# typeCounter.net
KiCad netlist of a schematic drawn in Altium Designer
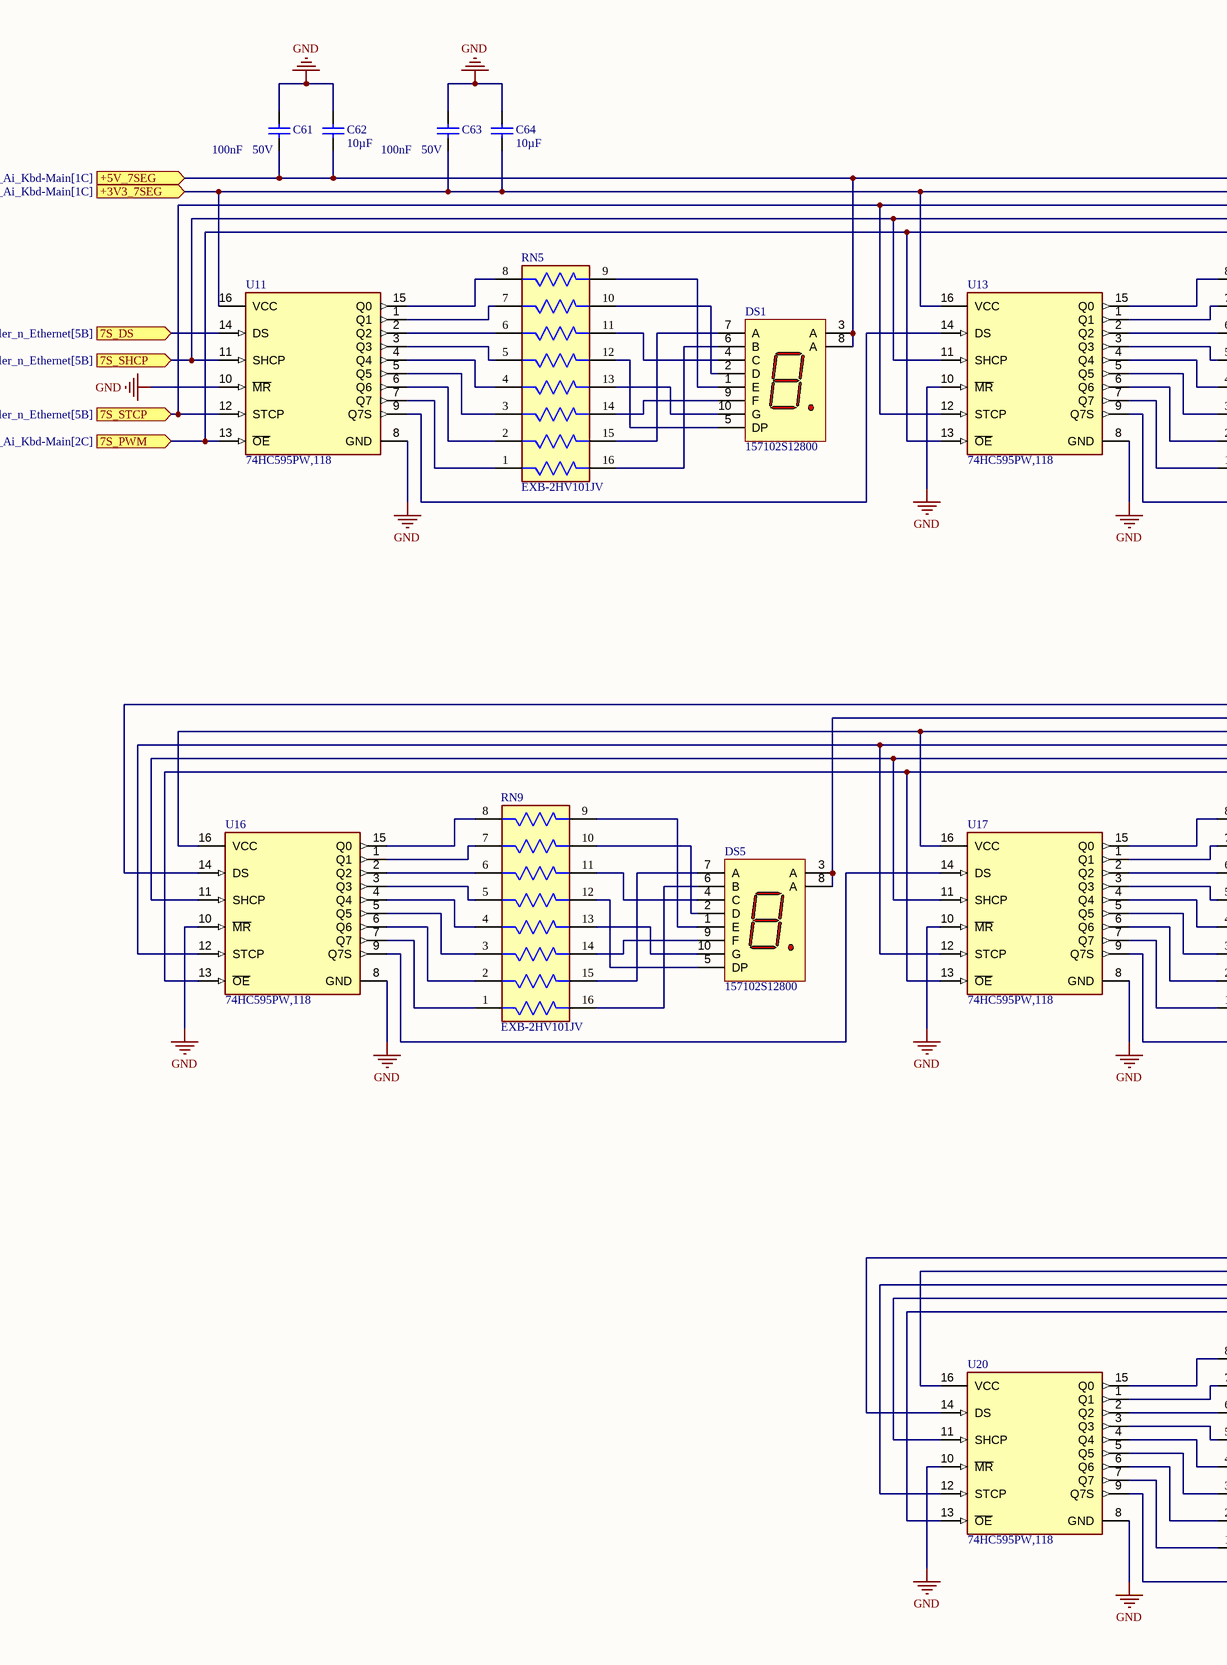
[diagram p0: typeCounter.SchDoc, left]
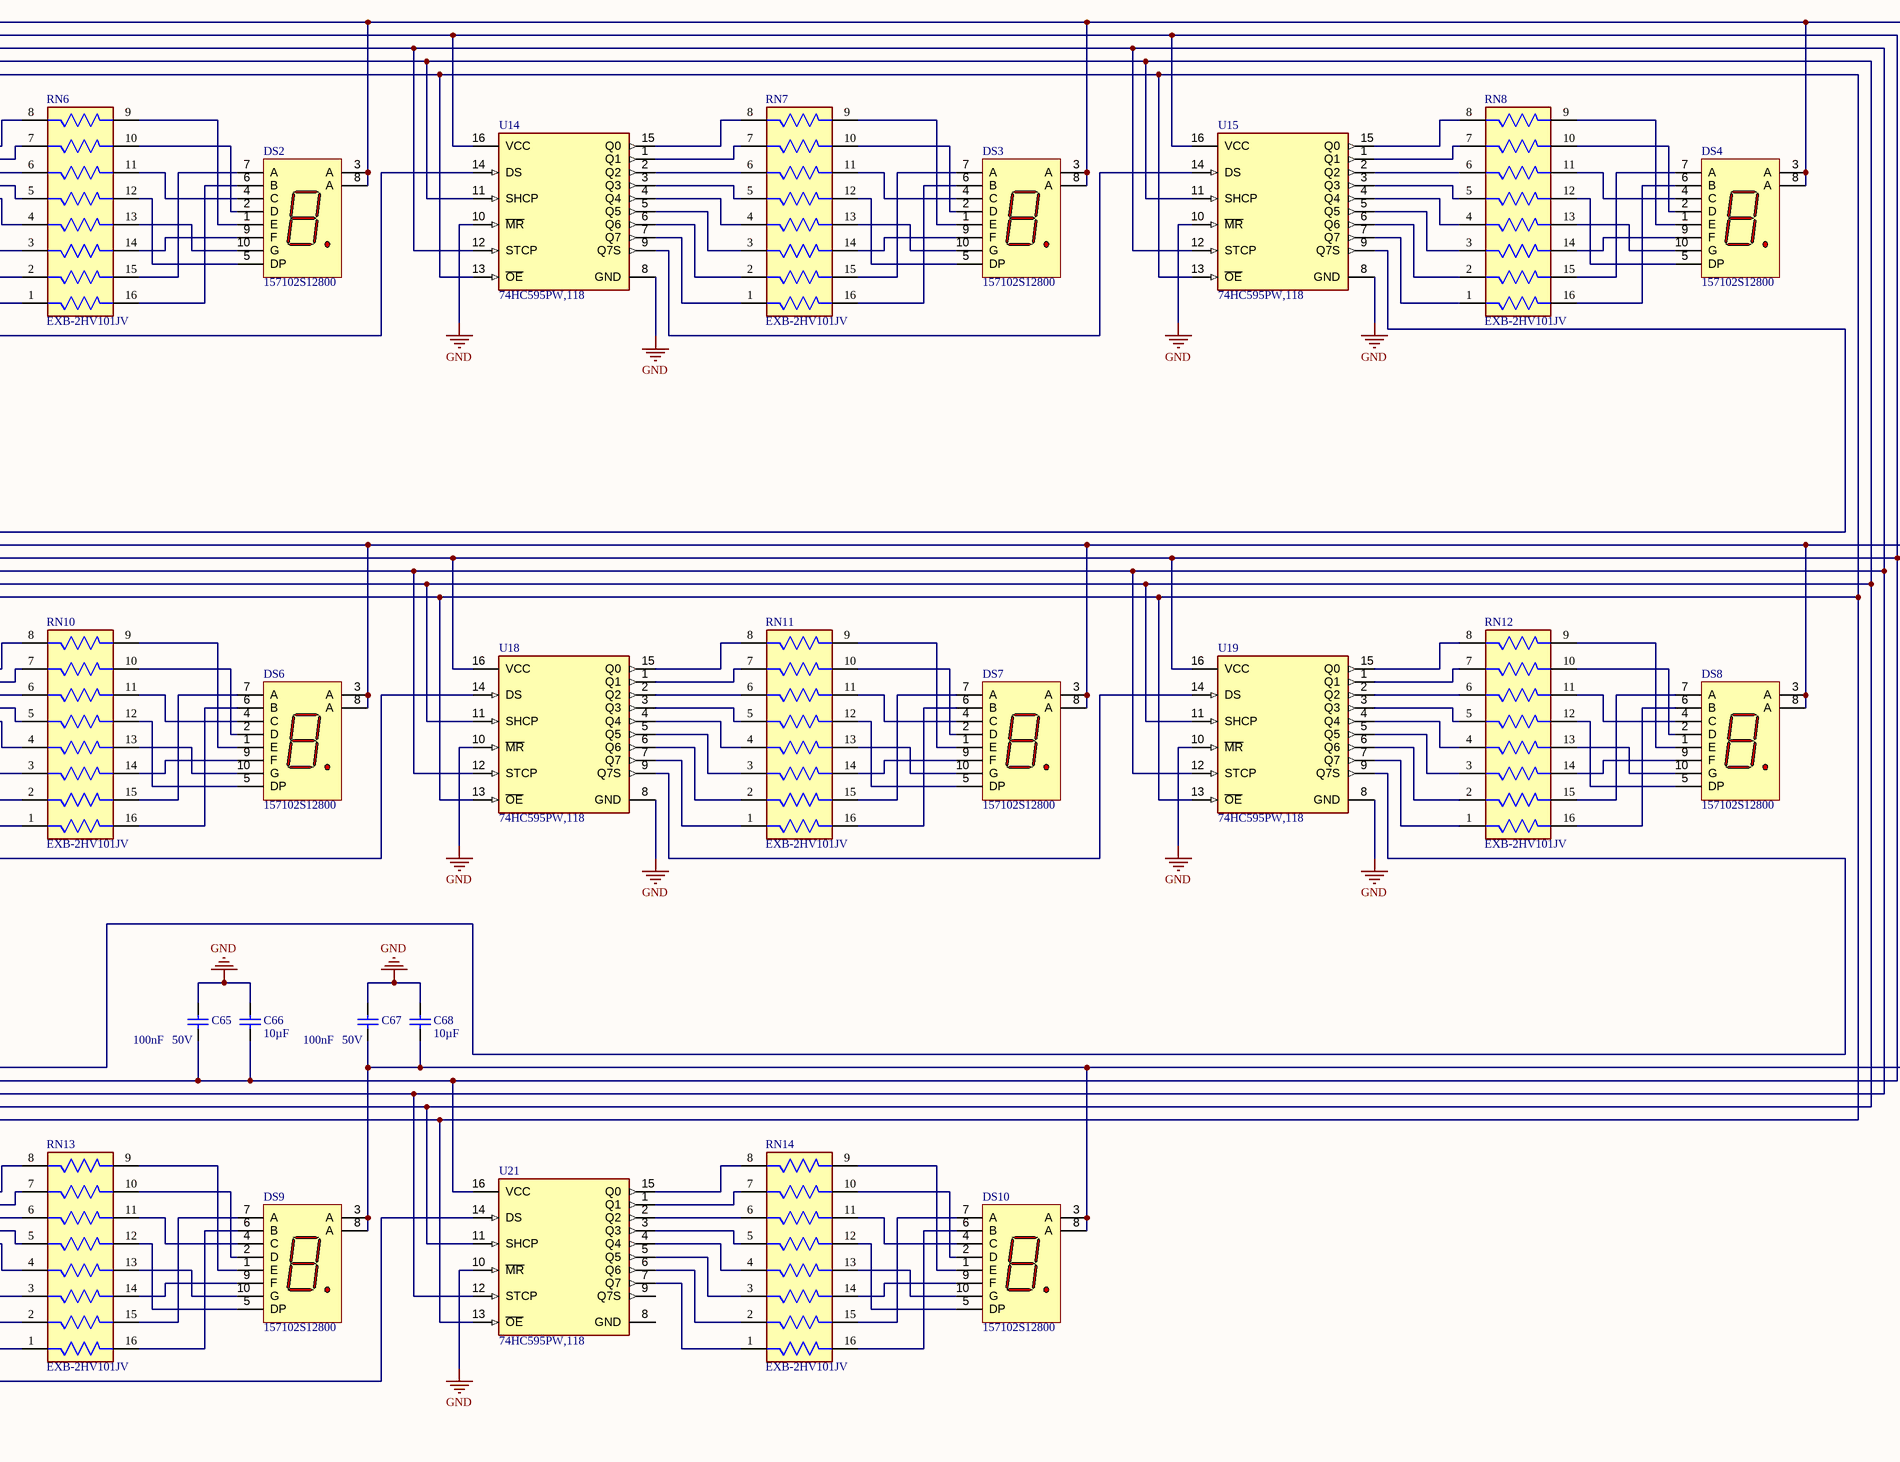
[diagram p1: typeCounter.SchDoc, right]

(export (version "E")
  (design (tool "Eeschema 10.0.6"))
  (components
    (comp (ref "C61")
      (value "885012206095")
      (footprint "WCAP-CSGP_0603_L1.6W0.8H0.8_Reflow")
      (description "WCAP-CSGP Multilayer Ceramic Chip Capacitor, General Purpose, size 0603, X7R, 100nF, 50VDC")
      (fields
        (field (name "CAPACITANCE") "100nF")
        (field (name "MANUFACTURER") "Wurth Elektronik")
        (field (name "RATED VOLTAGE (DC)") "50V")
      )
      (libsource (lib "Test365") (part "885012209047R"))
    )
    (comp (ref "C62")
      (value "885012106006")
      (footprint "WCAP-CSGP_0603_L1.6W0.8H0.8_Reflow")
      (description "WCAP-CSGP Multilayer Ceramic Chip Capacitor, General Purpose, size 0603, X5R, 10µF, 6.3VDC")
      (fields (field (name "MANUFACTURER") "Wurth Elektronik") (field (name "CAPACITANCE") "10µF"))
      (libsource (lib "Test365") (part "885012209047R"))
    )
    (comp (ref "C63")
      (value "885012206095")
      (footprint "WCAP-CSGP_0603_L1.6W0.8H0.8_Reflow")
      (description "WCAP-CSGP Multilayer Ceramic Chip Capacitor, General Purpose, size 0603, X7R, 100nF, 50VDC")
      (fields
        (field (name "CAPACITANCE") "100nF")
        (field (name "MANUFACTURER") "Wurth Elektronik")
        (field (name "RATED VOLTAGE (DC)") "50V")
      )
      (libsource (lib "Test365") (part "885012209047R"))
    )
    (comp (ref "C64")
      (value "885012106006")
      (footprint "WCAP-CSGP_0603_L1.6W0.8H0.8_Reflow")
      (description "WCAP-CSGP Multilayer Ceramic Chip Capacitor, General Purpose, size 0603, X5R, 10µF, 6.3VDC")
      (fields (field (name "MANUFACTURER") "Wurth Elektronik") (field (name "CAPACITANCE") "10µF"))
      (libsource (lib "Test365") (part "885012209047R"))
    )
    (comp (ref "C65")
      (value "885012206095")
      (footprint "WCAP-CSGP_0603_L1.6W0.8H0.8_Reflow")
      (description "WCAP-CSGP Multilayer Ceramic Chip Capacitor, General Purpose, size 0603, X7R, 100nF, 50VDC")
      (fields
        (field (name "CAPACITANCE") "100nF")
        (field (name "MANUFACTURER") "Wurth Elektronik")
        (field (name "RATED VOLTAGE (DC)") "50V")
      )
      (libsource (lib "Test365") (part "885012209047R"))
    )
    (comp (ref "C66")
      (value "885012106006")
      (footprint "WCAP-CSGP_0603_L1.6W0.8H0.8_Reflow")
      (description "WCAP-CSGP Multilayer Ceramic Chip Capacitor, General Purpose, size 0603, X5R, 10µF, 6.3VDC")
      (fields (field (name "MANUFACTURER") "Wurth Elektronik") (field (name "CAPACITANCE") "10µF"))
      (libsource (lib "Test365") (part "885012209047R"))
    )
    (comp (ref "C67")
      (value "885012206095")
      (footprint "WCAP-CSGP_0603_L1.6W0.8H0.8_Reflow")
      (description "WCAP-CSGP Multilayer Ceramic Chip Capacitor, General Purpose, size 0603, X7R, 100nF, 50VDC")
      (fields
        (field (name "CAPACITANCE") "100nF")
        (field (name "MANUFACTURER") "Wurth Elektronik")
        (field (name "RATED VOLTAGE (DC)") "50V")
      )
      (libsource (lib "Test365") (part "885012209047R"))
    )
    (comp (ref "C68")
      (value "885012106006")
      (footprint "WCAP-CSGP_0603_L1.6W0.8H0.8_Reflow")
      (description "WCAP-CSGP Multilayer Ceramic Chip Capacitor, General Purpose, size 0603, X5R, 10µF, 6.3VDC")
      (fields (field (name "MANUFACTURER") "Wurth Elektronik") (field (name "CAPACITANCE") "10µF"))
      (libsource (lib "Test365") (part "885012209047R"))
    )
    (comp (ref "DS1")
      (value "157102S12800")
      (footprint "WL-S7DS_L10W6.9H3")
      (description "157102S12800 WL-S7DS 7 Segments Display SMT Single Digit")
      (libsource (lib "Altium Content Vault") (part "7 Segments_Red_CA_type 1"))
    )
    (comp (ref "DS2")
      (value "157102S12800")
      (footprint "WL-S7DS_L10W6.9H3")
      (description "157102S12800 WL-S7DS 7 Segments Display SMT Single Digit")
      (libsource (lib "Altium Content Vault") (part "7 Segments_Red_CA_type 1"))
    )
    (comp (ref "DS3")
      (value "157102S12800")
      (footprint "WL-S7DS_L10W6.9H3")
      (description "157102S12800 WL-S7DS 7 Segments Display SMT Single Digit")
      (libsource (lib "Altium Content Vault") (part "7 Segments_Red_CA_type 1"))
    )
    (comp (ref "DS4")
      (value "157102S12800")
      (footprint "WL-S7DS_L10W6.9H3")
      (description "157102S12800 WL-S7DS 7 Segments Display SMT Single Digit")
      (libsource (lib "Altium Content Vault") (part "7 Segments_Red_CA_type 1"))
    )
    (comp (ref "DS5")
      (value "157102S12800")
      (footprint "WL-S7DS_L10W6.9H3")
      (description "157102S12800 WL-S7DS 7 Segments Display SMT Single Digit")
      (libsource (lib "Altium Content Vault") (part "7 Segments_Red_CA_type 1"))
    )
    (comp (ref "DS6")
      (value "157102S12800")
      (footprint "WL-S7DS_L10W6.9H3")
      (description "157102S12800 WL-S7DS 7 Segments Display SMT Single Digit")
      (libsource (lib "Altium Content Vault") (part "7 Segments_Red_CA_type 1"))
    )
    (comp (ref "DS7")
      (value "157102S12800")
      (footprint "WL-S7DS_L10W6.9H3")
      (description "157102S12800 WL-S7DS 7 Segments Display SMT Single Digit")
      (libsource (lib "Altium Content Vault") (part "7 Segments_Red_CA_type 1"))
    )
    (comp (ref "DS8")
      (value "157102S12800")
      (footprint "WL-S7DS_L10W6.9H3")
      (description "157102S12800 WL-S7DS 7 Segments Display SMT Single Digit")
      (libsource (lib "Altium Content Vault") (part "7 Segments_Red_CA_type 1"))
    )
    (comp (ref "DS9")
      (value "157102S12800")
      (footprint "WL-S7DS_L10W6.9H3")
      (description "157102S12800 WL-S7DS 7 Segments Display SMT Single Digit")
      (libsource (lib "Altium Content Vault") (part "7 Segments_Red_CA_type 1"))
    )
    (comp (ref "DS10")
      (value "157102S12800")
      (footprint "WL-S7DS_L10W6.9H3")
      (description "157102S12800 WL-S7DS 7 Segments Display SMT Single Digit")
      (libsource (lib "Altium Content Vault") (part "7 Segments_Red_CA_type 1"))
    )
    (comp (ref "RN5")
      (value "EXB-2HV101JV")
      (footprint "FP-EXB2HV-MFG")
      (description "RES ARRAY 8 RES 100 OHM 1506")
      (fields (field (name "TOLERANCE") "5%"))
      (libsource (lib "Altium Content Vault") (part "42159c3963beb1554014d4041102c8c"))
    )
    (comp (ref "RN6")
      (value "EXB-2HV101JV")
      (footprint "FP-EXB2HV-MFG")
      (description "RES ARRAY 8 RES 100 OHM 1506")
      (fields (field (name "TOLERANCE") "5%"))
      (libsource (lib "Altium Content Vault") (part "42159c3963beb1554014d4041102c8c"))
    )
    (comp (ref "RN7")
      (value "EXB-2HV101JV")
      (footprint "FP-EXB2HV-MFG")
      (description "RES ARRAY 8 RES 100 OHM 1506")
      (fields (field (name "TOLERANCE") "5%"))
      (libsource (lib "Altium Content Vault") (part "42159c3963beb1554014d4041102c8c"))
    )
    (comp (ref "RN8")
      (value "EXB-2HV101JV")
      (footprint "FP-EXB2HV-MFG")
      (description "RES ARRAY 8 RES 100 OHM 1506")
      (fields (field (name "TOLERANCE") "5%"))
      (libsource (lib "Altium Content Vault") (part "42159c3963beb1554014d4041102c8c"))
    )
    (comp (ref "RN9")
      (value "EXB-2HV101JV")
      (footprint "FP-EXB2HV-MFG")
      (description "RES ARRAY 8 RES 100 OHM 1506")
      (fields (field (name "TOLERANCE") "5%"))
      (libsource (lib "Altium Content Vault") (part "42159c3963beb1554014d4041102c8c"))
    )
    (comp (ref "RN10")
      (value "EXB-2HV101JV")
      (footprint "FP-EXB2HV-MFG")
      (description "RES ARRAY 8 RES 100 OHM 1506")
      (fields (field (name "TOLERANCE") "5%"))
      (libsource (lib "Altium Content Vault") (part "42159c3963beb1554014d4041102c8c"))
    )
    (comp (ref "RN11")
      (value "EXB-2HV101JV")
      (footprint "FP-EXB2HV-MFG")
      (description "RES ARRAY 8 RES 100 OHM 1506")
      (fields (field (name "TOLERANCE") "5%"))
      (libsource (lib "Altium Content Vault") (part "42159c3963beb1554014d4041102c8c"))
    )
    (comp (ref "RN12")
      (value "EXB-2HV101JV")
      (footprint "FP-EXB2HV-MFG")
      (description "RES ARRAY 8 RES 100 OHM 1506")
      (fields (field (name "TOLERANCE") "5%"))
      (libsource (lib "Altium Content Vault") (part "42159c3963beb1554014d4041102c8c"))
    )
    (comp (ref "RN13")
      (value "EXB-2HV101JV")
      (footprint "FP-EXB2HV-MFG")
      (description "RES ARRAY 8 RES 100 OHM 1506")
      (fields (field (name "TOLERANCE") "5%"))
      (libsource (lib "Altium Content Vault") (part "42159c3963beb1554014d4041102c8c"))
    )
    (comp (ref "RN14")
      (value "EXB-2HV101JV")
      (footprint "FP-EXB2HV-MFG")
      (description "RES ARRAY 8 RES 100 OHM 1506")
      (fields (field (name "TOLERANCE") "5%"))
      (libsource (lib "Altium Content Vault") (part "42159c3963beb1554014d4041102c8c"))
    )
    (comp (ref "U11")
      (value "74HC595PW,118")
      (footprint "FP-SOT403-1-MFG")
      (description "IC SHIFT REGISTER 8BIT 16TSSOP")
      (libsource (lib "Altium Content Vault") (part "27683e23285b137cd268a0f18c66bed"))
    )
    (comp (ref "U13")
      (value "74HC595PW,118")
      (footprint "FP-SOT403-1-MFG")
      (description "IC SHIFT REGISTER 8BIT 16TSSOP")
      (libsource (lib "Altium Content Vault") (part "27683e23285b137cd268a0f18c66bed"))
    )
    (comp (ref "U14")
      (value "74HC595PW,118")
      (footprint "FP-SOT403-1-MFG")
      (description "IC SHIFT REGISTER 8BIT 16TSSOP")
      (libsource (lib "Altium Content Vault") (part "27683e23285b137cd268a0f18c66bed"))
    )
    (comp (ref "U15")
      (value "74HC595PW,118")
      (footprint "FP-SOT403-1-MFG")
      (description "IC SHIFT REGISTER 8BIT 16TSSOP")
      (libsource (lib "Altium Content Vault") (part "27683e23285b137cd268a0f18c66bed"))
    )
    (comp (ref "U16")
      (value "74HC595PW,118")
      (footprint "FP-SOT403-1-MFG")
      (description "IC SHIFT REGISTER 8BIT 16TSSOP")
      (libsource (lib "Altium Content Vault") (part "27683e23285b137cd268a0f18c66bed"))
    )
    (comp (ref "U17")
      (value "74HC595PW,118")
      (footprint "FP-SOT403-1-MFG")
      (description "IC SHIFT REGISTER 8BIT 16TSSOP")
      (libsource (lib "Altium Content Vault") (part "27683e23285b137cd268a0f18c66bed"))
    )
    (comp (ref "U18")
      (value "74HC595PW,118")
      (footprint "FP-SOT403-1-MFG")
      (description "IC SHIFT REGISTER 8BIT 16TSSOP")
      (libsource (lib "Altium Content Vault") (part "27683e23285b137cd268a0f18c66bed"))
    )
    (comp (ref "U19")
      (value "74HC595PW,118")
      (footprint "FP-SOT403-1-MFG")
      (description "IC SHIFT REGISTER 8BIT 16TSSOP")
      (libsource (lib "Altium Content Vault") (part "27683e23285b137cd268a0f18c66bed"))
    )
    (comp (ref "U20")
      (value "74HC595PW,118")
      (footprint "FP-SOT403-1-MFG")
      (description "IC SHIFT REGISTER 8BIT 16TSSOP")
      (libsource (lib "Altium Content Vault") (part "27683e23285b137cd268a0f18c66bed"))
    )
    (comp (ref "U21")
      (value "74HC595PW,118")
      (footprint "FP-SOT403-1-MFG")
      (description "IC SHIFT REGISTER 8BIT 16TSSOP")
      (libsource (lib "Altium Content Vault") (part "27683e23285b137cd268a0f18c66bed"))
    )
  )
  (nets
    (net (code "1") (name "/+3V3_7SEG") (class "Default")
      (node (ref "C63") (pin "1") (pinfunction "1_1") (pintype "passive"))
      (node (ref "C64") (pin "1") (pinfunction "1_1") (pintype "passive"))
      (node (ref "C65") (pin "1") (pinfunction "1_1") (pintype "passive"))
      (node (ref "C66") (pin "1") (pinfunction "1_1") (pintype "passive"))
      (node (ref "U11") (pin "16") (pinfunction "VCC_16") (pintype "power_in"))
      (node (ref "U13") (pin "16") (pinfunction "VCC_16") (pintype "power_in"))
      (node (ref "U14") (pin "16") (pinfunction "VCC_16") (pintype "power_in"))
      (node (ref "U15") (pin "16") (pinfunction "VCC_16") (pintype "power_in"))
      (node (ref "U16") (pin "16") (pinfunction "VCC_16") (pintype "power_in"))
      (node (ref "U17") (pin "16") (pinfunction "VCC_16") (pintype "power_in"))
      (node (ref "U18") (pin "16") (pinfunction "VCC_16") (pintype "power_in"))
      (node (ref "U19") (pin "16") (pinfunction "VCC_16") (pintype "power_in"))
      (node (ref "U20") (pin "16") (pinfunction "VCC_16") (pintype "power_in"))
      (node (ref "U21") (pin "16") (pinfunction "VCC_16") (pintype "power_in"))
    )
    (net (code "2") (name "/+5V_7SEG") (class "Default")
      (node (ref "C61") (pin "1") (pinfunction "1_1") (pintype "passive"))
      (node (ref "C62") (pin "1") (pinfunction "1_1") (pintype "passive"))
      (node (ref "C67") (pin "1") (pinfunction "1_1") (pintype "passive"))
      (node (ref "C68") (pin "1") (pinfunction "1_1") (pintype "passive"))
      (node (ref "DS1") (pin "3") (pinfunction "A_3") (pintype "passive"))
      (node (ref "DS1") (pin "8") (pinfunction "A_8") (pintype "passive"))
      (node (ref "DS10") (pin "3") (pinfunction "A_3") (pintype "passive"))
      (node (ref "DS10") (pin "8") (pinfunction "A_8") (pintype "passive"))
      (node (ref "DS2") (pin "3") (pinfunction "A_3") (pintype "passive"))
      (node (ref "DS2") (pin "8") (pinfunction "A_8") (pintype "passive"))
      (node (ref "DS3") (pin "3") (pinfunction "A_3") (pintype "passive"))
      (node (ref "DS3") (pin "8") (pinfunction "A_8") (pintype "passive"))
      (node (ref "DS4") (pin "3") (pinfunction "A_3") (pintype "passive"))
      (node (ref "DS4") (pin "8") (pinfunction "A_8") (pintype "passive"))
      (node (ref "DS5") (pin "3") (pinfunction "A_3") (pintype "passive"))
      (node (ref "DS5") (pin "8") (pinfunction "A_8") (pintype "passive"))
      (node (ref "DS6") (pin "3") (pinfunction "A_3") (pintype "passive"))
      (node (ref "DS6") (pin "8") (pinfunction "A_8") (pintype "passive"))
      (node (ref "DS7") (pin "3") (pinfunction "A_3") (pintype "passive"))
      (node (ref "DS7") (pin "8") (pinfunction "A_8") (pintype "passive"))
      (node (ref "DS8") (pin "3") (pinfunction "A_3") (pintype "passive"))
      (node (ref "DS8") (pin "8") (pinfunction "A_8") (pintype "passive"))
      (node (ref "DS9") (pin "3") (pinfunction "A_3") (pintype "passive"))
      (node (ref "DS9") (pin "8") (pinfunction "A_8") (pintype "passive"))
    )
    (net (code "3") (name "/7S_DS") (class "Default")
      (node (ref "U11") (pin "14") (pinfunction "DS_14") (pintype "input"))
    )
    (net (code "4") (name "/7S_PWM") (class "Default")
      (node (ref "U11") (pin "13") (pinfunction "~{OE}_13") (pintype "input"))
      (node (ref "U13") (pin "13") (pinfunction "~{OE}_13") (pintype "input"))
      (node (ref "U14") (pin "13") (pinfunction "~{OE}_13") (pintype "input"))
      (node (ref "U15") (pin "13") (pinfunction "~{OE}_13") (pintype "input"))
      (node (ref "U16") (pin "13") (pinfunction "~{OE}_13") (pintype "input"))
      (node (ref "U17") (pin "13") (pinfunction "~{OE}_13") (pintype "input"))
      (node (ref "U18") (pin "13") (pinfunction "~{OE}_13") (pintype "input"))
      (node (ref "U19") (pin "13") (pinfunction "~{OE}_13") (pintype "input"))
      (node (ref "U20") (pin "13") (pinfunction "~{OE}_13") (pintype "input"))
      (node (ref "U21") (pin "13") (pinfunction "~{OE}_13") (pintype "input"))
    )
    (net (code "5") (name "/7S_SHCP") (class "Default")
      (node (ref "U11") (pin "11") (pinfunction "SHCP_11") (pintype "input"))
      (node (ref "U13") (pin "11") (pinfunction "SHCP_11") (pintype "input"))
      (node (ref "U14") (pin "11") (pinfunction "SHCP_11") (pintype "input"))
      (node (ref "U15") (pin "11") (pinfunction "SHCP_11") (pintype "input"))
      (node (ref "U16") (pin "11") (pinfunction "SHCP_11") (pintype "input"))
      (node (ref "U17") (pin "11") (pinfunction "SHCP_11") (pintype "input"))
      (node (ref "U18") (pin "11") (pinfunction "SHCP_11") (pintype "input"))
      (node (ref "U19") (pin "11") (pinfunction "SHCP_11") (pintype "input"))
      (node (ref "U20") (pin "11") (pinfunction "SHCP_11") (pintype "input"))
      (node (ref "U21") (pin "11") (pinfunction "SHCP_11") (pintype "input"))
    )
    (net (code "6") (name "/7S_STCP") (class "Default")
      (node (ref "U11") (pin "12") (pinfunction "STCP_12") (pintype "input"))
      (node (ref "U13") (pin "12") (pinfunction "STCP_12") (pintype "input"))
      (node (ref "U14") (pin "12") (pinfunction "STCP_12") (pintype "input"))
      (node (ref "U15") (pin "12") (pinfunction "STCP_12") (pintype "input"))
      (node (ref "U16") (pin "12") (pinfunction "STCP_12") (pintype "input"))
      (node (ref "U17") (pin "12") (pinfunction "STCP_12") (pintype "input"))
      (node (ref "U18") (pin "12") (pinfunction "STCP_12") (pintype "input"))
      (node (ref "U19") (pin "12") (pinfunction "STCP_12") (pintype "input"))
      (node (ref "U20") (pin "12") (pinfunction "STCP_12") (pintype "input"))
      (node (ref "U21") (pin "12") (pinfunction "STCP_12") (pintype "input"))
    )
    (net (code "7") (name "GND") (class "Default")
      (node (ref "C61") (pin "2") (pinfunction "2_2") (pintype "passive"))
      (node (ref "C62") (pin "2") (pinfunction "2_2") (pintype "passive"))
      (node (ref "C63") (pin "2") (pinfunction "2_2") (pintype "passive"))
      (node (ref "C64") (pin "2") (pinfunction "2_2") (pintype "passive"))
      (node (ref "C65") (pin "2") (pinfunction "2_2") (pintype "passive"))
      (node (ref "C66") (pin "2") (pinfunction "2_2") (pintype "passive"))
      (node (ref "C67") (pin "2") (pinfunction "2_2") (pintype "passive"))
      (node (ref "C68") (pin "2") (pinfunction "2_2") (pintype "passive"))
      (node (ref "U11") (pin "10") (pinfunction "~{MR}_10") (pintype "input"))
      (node (ref "U11") (pin "8") (pinfunction "GND_8") (pintype "power_in"))
      (node (ref "U13") (pin "10") (pinfunction "~{MR}_10") (pintype "input"))
      (node (ref "U13") (pin "8") (pinfunction "GND_8") (pintype "power_in"))
      (node (ref "U14") (pin "10") (pinfunction "~{MR}_10") (pintype "input"))
      (node (ref "U14") (pin "8") (pinfunction "GND_8") (pintype "power_in"))
      (node (ref "U15") (pin "10") (pinfunction "~{MR}_10") (pintype "input"))
      (node (ref "U15") (pin "8") (pinfunction "GND_8") (pintype "power_in"))
      (node (ref "U16") (pin "10") (pinfunction "~{MR}_10") (pintype "input"))
      (node (ref "U16") (pin "8") (pinfunction "GND_8") (pintype "power_in"))
      (node (ref "U17") (pin "10") (pinfunction "~{MR}_10") (pintype "input"))
      (node (ref "U17") (pin "8") (pinfunction "GND_8") (pintype "power_in"))
      (node (ref "U18") (pin "10") (pinfunction "~{MR}_10") (pintype "input"))
      (node (ref "U18") (pin "8") (pinfunction "GND_8") (pintype "power_in"))
      (node (ref "U19") (pin "10") (pinfunction "~{MR}_10") (pintype "input"))
      (node (ref "U19") (pin "8") (pinfunction "GND_8") (pintype "power_in"))
      (node (ref "U20") (pin "10") (pinfunction "~{MR}_10") (pintype "input"))
      (node (ref "U20") (pin "8") (pinfunction "GND_8") (pintype "power_in"))
      (node (ref "U21") (pin "10") (pinfunction "~{MR}_10") (pintype "input"))
    )
    (net (code "8") (name "Net-(DS1-A-Pad7)") (class "Default")
      (node (ref "DS1") (pin "7") (pinfunction "A_7") (pintype "passive"))
      (node (ref "RN5") (pin "15") (pinfunction "15_15") (pintype "passive"))
    )
    (net (code "9") (name "Net-(DS1-B)") (class "Default")
      (node (ref "DS1") (pin "6") (pinfunction "B_6") (pintype "passive"))
      (node (ref "RN5") (pin "16") (pinfunction "16_16") (pintype "passive"))
    )
    (net (code "10") (name "Net-(DS1-C)") (class "Default")
      (node (ref "DS1") (pin "4") (pinfunction "C_4") (pintype "passive"))
      (node (ref "RN5") (pin "11") (pinfunction "11_11") (pintype "passive"))
    )
    (net (code "11") (name "Net-(DS1-D)") (class "Default")
      (node (ref "DS1") (pin "2") (pinfunction "D_2") (pintype "passive"))
      (node (ref "RN5") (pin "10") (pinfunction "10_10") (pintype "passive"))
    )
    (net (code "12") (name "Net-(DS1-DP)") (class "Default")
      (node (ref "DS1") (pin "5") (pinfunction "DP_5") (pintype "passive"))
      (node (ref "RN5") (pin "12") (pinfunction "12_12") (pintype "passive"))
    )
    (net (code "13") (name "Net-(DS1-E)") (class "Default")
      (node (ref "DS1") (pin "1") (pinfunction "E_1") (pintype "passive"))
      (node (ref "RN5") (pin "9") (pinfunction "9_9") (pintype "passive"))
    )
    (net (code "14") (name "Net-(DS1-F)") (class "Default")
      (node (ref "DS1") (pin "9") (pinfunction "F_9") (pintype "passive"))
      (node (ref "RN5") (pin "14") (pinfunction "14_14") (pintype "passive"))
    )
    (net (code "15") (name "Net-(DS1-G)") (class "Default")
      (node (ref "DS1") (pin "10") (pinfunction "G_10") (pintype "passive"))
      (node (ref "RN5") (pin "13") (pinfunction "13_13") (pintype "passive"))
    )
    (net (code "16") (name "Net-(DS2-A-Pad7)") (class "Default")
      (node (ref "DS2") (pin "7") (pinfunction "A_7") (pintype "passive"))
      (node (ref "RN6") (pin "15") (pinfunction "15_15") (pintype "passive"))
    )
    (net (code "17") (name "Net-(DS2-B)") (class "Default")
      (node (ref "DS2") (pin "6") (pinfunction "B_6") (pintype "passive"))
      (node (ref "RN6") (pin "16") (pinfunction "16_16") (pintype "passive"))
    )
    (net (code "18") (name "Net-(DS2-C)") (class "Default")
      (node (ref "DS2") (pin "4") (pinfunction "C_4") (pintype "passive"))
      (node (ref "RN6") (pin "11") (pinfunction "11_11") (pintype "passive"))
    )
    (net (code "19") (name "Net-(DS2-D)") (class "Default")
      (node (ref "DS2") (pin "2") (pinfunction "D_2") (pintype "passive"))
      (node (ref "RN6") (pin "10") (pinfunction "10_10") (pintype "passive"))
    )
    (net (code "20") (name "Net-(DS2-DP)") (class "Default")
      (node (ref "DS2") (pin "5") (pinfunction "DP_5") (pintype "passive"))
      (node (ref "RN6") (pin "12") (pinfunction "12_12") (pintype "passive"))
    )
    (net (code "21") (name "Net-(DS2-E)") (class "Default")
      (node (ref "DS2") (pin "1") (pinfunction "E_1") (pintype "passive"))
      (node (ref "RN6") (pin "9") (pinfunction "9_9") (pintype "passive"))
    )
    (net (code "22") (name "Net-(DS2-F)") (class "Default")
      (node (ref "DS2") (pin "9") (pinfunction "F_9") (pintype "passive"))
      (node (ref "RN6") (pin "14") (pinfunction "14_14") (pintype "passive"))
    )
    (net (code "23") (name "Net-(DS2-G)") (class "Default")
      (node (ref "DS2") (pin "10") (pinfunction "G_10") (pintype "passive"))
      (node (ref "RN6") (pin "13") (pinfunction "13_13") (pintype "passive"))
    )
    (net (code "24") (name "Net-(DS3-A-Pad7)") (class "Default")
      (node (ref "DS3") (pin "7") (pinfunction "A_7") (pintype "passive"))
      (node (ref "RN7") (pin "15") (pinfunction "15_15") (pintype "passive"))
    )
    (net (code "25") (name "Net-(DS3-B)") (class "Default")
      (node (ref "DS3") (pin "6") (pinfunction "B_6") (pintype "passive"))
      (node (ref "RN7") (pin "16") (pinfunction "16_16") (pintype "passive"))
    )
    (net (code "26") (name "Net-(DS3-C)") (class "Default")
      (node (ref "DS3") (pin "4") (pinfunction "C_4") (pintype "passive"))
      (node (ref "RN7") (pin "11") (pinfunction "11_11") (pintype "passive"))
    )
    (net (code "27") (name "Net-(DS3-D)") (class "Default")
      (node (ref "DS3") (pin "2") (pinfunction "D_2") (pintype "passive"))
      (node (ref "RN7") (pin "10") (pinfunction "10_10") (pintype "passive"))
    )
    (net (code "28") (name "Net-(DS3-DP)") (class "Default")
      (node (ref "DS3") (pin "5") (pinfunction "DP_5") (pintype "passive"))
      (node (ref "RN7") (pin "12") (pinfunction "12_12") (pintype "passive"))
    )
    (net (code "29") (name "Net-(DS3-E)") (class "Default")
      (node (ref "DS3") (pin "1") (pinfunction "E_1") (pintype "passive"))
      (node (ref "RN7") (pin "9") (pinfunction "9_9") (pintype "passive"))
    )
    (net (code "30") (name "Net-(DS3-F)") (class "Default")
      (node (ref "DS3") (pin "9") (pinfunction "F_9") (pintype "passive"))
      (node (ref "RN7") (pin "14") (pinfunction "14_14") (pintype "passive"))
    )
    (net (code "31") (name "Net-(DS3-G)") (class "Default")
      (node (ref "DS3") (pin "10") (pinfunction "G_10") (pintype "passive"))
      (node (ref "RN7") (pin "13") (pinfunction "13_13") (pintype "passive"))
    )
    (net (code "32") (name "Net-(DS4-A-Pad7)") (class "Default")
      (node (ref "DS4") (pin "7") (pinfunction "A_7") (pintype "passive"))
      (node (ref "RN8") (pin "15") (pinfunction "15_15") (pintype "passive"))
    )
    (net (code "33") (name "Net-(DS4-B)") (class "Default")
      (node (ref "DS4") (pin "6") (pinfunction "B_6") (pintype "passive"))
      (node (ref "RN8") (pin "16") (pinfunction "16_16") (pintype "passive"))
    )
    (net (code "34") (name "Net-(DS4-C)") (class "Default")
      (node (ref "DS4") (pin "4") (pinfunction "C_4") (pintype "passive"))
      (node (ref "RN8") (pin "11") (pinfunction "11_11") (pintype "passive"))
    )
    (net (code "35") (name "Net-(DS4-D)") (class "Default")
      (node (ref "DS4") (pin "2") (pinfunction "D_2") (pintype "passive"))
      (node (ref "RN8") (pin "10") (pinfunction "10_10") (pintype "passive"))
    )
    (net (code "36") (name "Net-(DS4-DP)") (class "Default")
      (node (ref "DS4") (pin "5") (pinfunction "DP_5") (pintype "passive"))
      (node (ref "RN8") (pin "12") (pinfunction "12_12") (pintype "passive"))
    )
    (net (code "37") (name "Net-(DS4-E)") (class "Default")
      (node (ref "DS4") (pin "1") (pinfunction "E_1") (pintype "passive"))
      (node (ref "RN8") (pin "9") (pinfunction "9_9") (pintype "passive"))
    )
    (net (code "38") (name "Net-(DS4-F)") (class "Default")
      (node (ref "DS4") (pin "9") (pinfunction "F_9") (pintype "passive"))
      (node (ref "RN8") (pin "14") (pinfunction "14_14") (pintype "passive"))
    )
    (net (code "39") (name "Net-(DS4-G)") (class "Default")
      (node (ref "DS4") (pin "10") (pinfunction "G_10") (pintype "passive"))
      (node (ref "RN8") (pin "13") (pinfunction "13_13") (pintype "passive"))
    )
    (net (code "40") (name "Net-(DS5-A-Pad7)") (class "Default")
      (node (ref "DS5") (pin "7") (pinfunction "A_7") (pintype "passive"))
      (node (ref "RN9") (pin "15") (pinfunction "15_15") (pintype "passive"))
    )
    (net (code "41") (name "Net-(DS5-B)") (class "Default")
      (node (ref "DS5") (pin "6") (pinfunction "B_6") (pintype "passive"))
      (node (ref "RN9") (pin "16") (pinfunction "16_16") (pintype "passive"))
    )
    (net (code "42") (name "Net-(DS5-C)") (class "Default")
      (node (ref "DS5") (pin "4") (pinfunction "C_4") (pintype "passive"))
      (node (ref "RN9") (pin "11") (pinfunction "11_11") (pintype "passive"))
    )
    (net (code "43") (name "Net-(DS5-D)") (class "Default")
      (node (ref "DS5") (pin "2") (pinfunction "D_2") (pintype "passive"))
      (node (ref "RN9") (pin "10") (pinfunction "10_10") (pintype "passive"))
    )
    (net (code "44") (name "Net-(DS5-DP)") (class "Default")
      (node (ref "DS5") (pin "5") (pinfunction "DP_5") (pintype "passive"))
      (node (ref "RN9") (pin "12") (pinfunction "12_12") (pintype "passive"))
    )
    (net (code "45") (name "Net-(DS5-E)") (class "Default")
      (node (ref "DS5") (pin "1") (pinfunction "E_1") (pintype "passive"))
      (node (ref "RN9") (pin "9") (pinfunction "9_9") (pintype "passive"))
    )
    (net (code "46") (name "Net-(DS5-F)") (class "Default")
      (node (ref "DS5") (pin "9") (pinfunction "F_9") (pintype "passive"))
      (node (ref "RN9") (pin "14") (pinfunction "14_14") (pintype "passive"))
    )
    (net (code "47") (name "Net-(DS5-G)") (class "Default")
      (node (ref "DS5") (pin "10") (pinfunction "G_10") (pintype "passive"))
      (node (ref "RN9") (pin "13") (pinfunction "13_13") (pintype "passive"))
    )
    (net (code "48") (name "Net-(DS6-A-Pad7)") (class "Default")
      (node (ref "DS6") (pin "7") (pinfunction "A_7") (pintype "passive"))
      (node (ref "RN10") (pin "15") (pinfunction "15_15") (pintype "passive"))
    )
    (net (code "49") (name "Net-(DS6-B)") (class "Default")
      (node (ref "DS6") (pin "6") (pinfunction "B_6") (pintype "passive"))
      (node (ref "RN10") (pin "16") (pinfunction "16_16") (pintype "passive"))
    )
    (net (code "50") (name "Net-(DS6-C)") (class "Default")
      (node (ref "DS6") (pin "4") (pinfunction "C_4") (pintype "passive"))
      (node (ref "RN10") (pin "11") (pinfunction "11_11") (pintype "passive"))
    )
    (net (code "51") (name "Net-(DS6-D)") (class "Default")
      (node (ref "DS6") (pin "2") (pinfunction "D_2") (pintype "passive"))
      (node (ref "RN10") (pin "10") (pinfunction "10_10") (pintype "passive"))
    )
    (net (code "52") (name "Net-(DS6-DP)") (class "Default")
      (node (ref "DS6") (pin "5") (pinfunction "DP_5") (pintype "passive"))
      (node (ref "RN10") (pin "12") (pinfunction "12_12") (pintype "passive"))
    )
    (net (code "53") (name "Net-(DS6-E)") (class "Default")
      (node (ref "DS6") (pin "1") (pinfunction "E_1") (pintype "passive"))
      (node (ref "RN10") (pin "9") (pinfunction "9_9") (pintype "passive"))
    )
    (net (code "54") (name "Net-(DS6-F)") (class "Default")
      (node (ref "DS6") (pin "9") (pinfunction "F_9") (pintype "passive"))
      (node (ref "RN10") (pin "14") (pinfunction "14_14") (pintype "passive"))
    )
    (net (code "55") (name "Net-(DS6-G)") (class "Default")
      (node (ref "DS6") (pin "10") (pinfunction "G_10") (pintype "passive"))
      (node (ref "RN10") (pin "13") (pinfunction "13_13") (pintype "passive"))
    )
    (net (code "56") (name "Net-(DS7-A-Pad7)") (class "Default")
      (node (ref "DS7") (pin "7") (pinfunction "A_7") (pintype "passive"))
      (node (ref "RN11") (pin "15") (pinfunction "15_15") (pintype "passive"))
    )
    (net (code "57") (name "Net-(DS7-B)") (class "Default")
      (node (ref "DS7") (pin "6") (pinfunction "B_6") (pintype "passive"))
      (node (ref "RN11") (pin "16") (pinfunction "16_16") (pintype "passive"))
    )
    (net (code "58") (name "Net-(DS7-C)") (class "Default")
      (node (ref "DS7") (pin "4") (pinfunction "C_4") (pintype "passive"))
      (node (ref "RN11") (pin "11") (pinfunction "11_11") (pintype "passive"))
    )
    (net (code "59") (name "Net-(DS7-D)") (class "Default")
      (node (ref "DS7") (pin "2") (pinfunction "D_2") (pintype "passive"))
      (node (ref "RN11") (pin "10") (pinfunction "10_10") (pintype "passive"))
    )
    (net (code "60") (name "Net-(DS7-DP)") (class "Default")
      (node (ref "DS7") (pin "5") (pinfunction "DP_5") (pintype "passive"))
      (node (ref "RN11") (pin "12") (pinfunction "12_12") (pintype "passive"))
    )
    (net (code "61") (name "Net-(DS7-E)") (class "Default")
      (node (ref "DS7") (pin "1") (pinfunction "E_1") (pintype "passive"))
      (node (ref "RN11") (pin "9") (pinfunction "9_9") (pintype "passive"))
    )
    (net (code "62") (name "Net-(DS7-F)") (class "Default")
      (node (ref "DS7") (pin "9") (pinfunction "F_9") (pintype "passive"))
      (node (ref "RN11") (pin "14") (pinfunction "14_14") (pintype "passive"))
    )
    (net (code "63") (name "Net-(DS7-G)") (class "Default")
      (node (ref "DS7") (pin "10") (pinfunction "G_10") (pintype "passive"))
      (node (ref "RN11") (pin "13") (pinfunction "13_13") (pintype "passive"))
    )
    (net (code "64") (name "Net-(DS8-A-Pad7)") (class "Default")
      (node (ref "DS8") (pin "7") (pinfunction "A_7") (pintype "passive"))
      (node (ref "RN12") (pin "15") (pinfunction "15_15") (pintype "passive"))
    )
    (net (code "65") (name "Net-(DS8-B)") (class "Default")
      (node (ref "DS8") (pin "6") (pinfunction "B_6") (pintype "passive"))
      (node (ref "RN12") (pin "16") (pinfunction "16_16") (pintype "passive"))
    )
    (net (code "66") (name "Net-(DS8-C)") (class "Default")
      (node (ref "DS8") (pin "4") (pinfunction "C_4") (pintype "passive"))
      (node (ref "RN12") (pin "11") (pinfunction "11_11") (pintype "passive"))
    )
    (net (code "67") (name "Net-(DS8-D)") (class "Default")
      (node (ref "DS8") (pin "2") (pinfunction "D_2") (pintype "passive"))
      (node (ref "RN12") (pin "10") (pinfunction "10_10") (pintype "passive"))
    )
    (net (code "68") (name "Net-(DS8-DP)") (class "Default")
      (node (ref "DS8") (pin "5") (pinfunction "DP_5") (pintype "passive"))
      (node (ref "RN12") (pin "12") (pinfunction "12_12") (pintype "passive"))
    )
    (net (code "69") (name "Net-(DS8-E)") (class "Default")
      (node (ref "DS8") (pin "1") (pinfunction "E_1") (pintype "passive"))
      (node (ref "RN12") (pin "9") (pinfunction "9_9") (pintype "passive"))
    )
    (net (code "70") (name "Net-(DS8-F)") (class "Default")
      (node (ref "DS8") (pin "9") (pinfunction "F_9") (pintype "passive"))
      (node (ref "RN12") (pin "14") (pinfunction "14_14") (pintype "passive"))
    )
    (net (code "71") (name "Net-(DS8-G)") (class "Default")
      (node (ref "DS8") (pin "10") (pinfunction "G_10") (pintype "passive"))
      (node (ref "RN12") (pin "13") (pinfunction "13_13") (pintype "passive"))
    )
    (net (code "72") (name "Net-(DS9-A-Pad7)") (class "Default")
      (node (ref "DS9") (pin "7") (pinfunction "A_7") (pintype "passive"))
      (node (ref "RN13") (pin "15") (pinfunction "15_15") (pintype "passive"))
    )
    (net (code "73") (name "Net-(DS9-B)") (class "Default")
      (node (ref "DS9") (pin "6") (pinfunction "B_6") (pintype "passive"))
      (node (ref "RN13") (pin "16") (pinfunction "16_16") (pintype "passive"))
    )
    (net (code "74") (name "Net-(DS9-C)") (class "Default")
      (node (ref "DS9") (pin "4") (pinfunction "C_4") (pintype "passive"))
      (node (ref "RN13") (pin "11") (pinfunction "11_11") (pintype "passive"))
    )
    (net (code "75") (name "Net-(DS9-D)") (class "Default")
      (node (ref "DS9") (pin "2") (pinfunction "D_2") (pintype "passive"))
      (node (ref "RN13") (pin "10") (pinfunction "10_10") (pintype "passive"))
    )
    (net (code "76") (name "Net-(DS9-DP)") (class "Default")
      (node (ref "DS9") (pin "5") (pinfunction "DP_5") (pintype "passive"))
      (node (ref "RN13") (pin "12") (pinfunction "12_12") (pintype "passive"))
    )
    (net (code "77") (name "Net-(DS9-E)") (class "Default")
      (node (ref "DS9") (pin "1") (pinfunction "E_1") (pintype "passive"))
      (node (ref "RN13") (pin "9") (pinfunction "9_9") (pintype "passive"))
    )
    (net (code "78") (name "Net-(DS9-F)") (class "Default")
      (node (ref "DS9") (pin "9") (pinfunction "F_9") (pintype "passive"))
      (node (ref "RN13") (pin "14") (pinfunction "14_14") (pintype "passive"))
    )
    (net (code "79") (name "Net-(DS9-G)") (class "Default")
      (node (ref "DS9") (pin "10") (pinfunction "G_10") (pintype "passive"))
      (node (ref "RN13") (pin "13") (pinfunction "13_13") (pintype "passive"))
    )
    (net (code "80") (name "Net-(DS10-A-Pad7)") (class "Default")
      (node (ref "DS10") (pin "7") (pinfunction "A_7") (pintype "passive"))
      (node (ref "RN14") (pin "15") (pinfunction "15_15") (pintype "passive"))
    )
    (net (code "81") (name "Net-(DS10-B)") (class "Default")
      (node (ref "DS10") (pin "6") (pinfunction "B_6") (pintype "passive"))
      (node (ref "RN14") (pin "16") (pinfunction "16_16") (pintype "passive"))
    )
    (net (code "82") (name "Net-(DS10-C)") (class "Default")
      (node (ref "DS10") (pin "4") (pinfunction "C_4") (pintype "passive"))
      (node (ref "RN14") (pin "11") (pinfunction "11_11") (pintype "passive"))
    )
    (net (code "83") (name "Net-(DS10-D)") (class "Default")
      (node (ref "DS10") (pin "2") (pinfunction "D_2") (pintype "passive"))
      (node (ref "RN14") (pin "10") (pinfunction "10_10") (pintype "passive"))
    )
    (net (code "84") (name "Net-(DS10-DP)") (class "Default")
      (node (ref "DS10") (pin "5") (pinfunction "DP_5") (pintype "passive"))
      (node (ref "RN14") (pin "12") (pinfunction "12_12") (pintype "passive"))
    )
    (net (code "85") (name "Net-(DS10-E)") (class "Default")
      (node (ref "DS10") (pin "1") (pinfunction "E_1") (pintype "passive"))
      (node (ref "RN14") (pin "9") (pinfunction "9_9") (pintype "passive"))
    )
    (net (code "86") (name "Net-(DS10-F)") (class "Default")
      (node (ref "DS10") (pin "9") (pinfunction "F_9") (pintype "passive"))
      (node (ref "RN14") (pin "14") (pinfunction "14_14") (pintype "passive"))
    )
    (net (code "87") (name "Net-(DS10-G)") (class "Default")
      (node (ref "DS10") (pin "10") (pinfunction "G_10") (pintype "passive"))
      (node (ref "RN14") (pin "13") (pinfunction "13_13") (pintype "passive"))
    )
    (net (code "88") (name "Net-(U11-Q0)") (class "Default")
      (node (ref "RN5") (pin "8") (pinfunction "8_8") (pintype "passive"))
      (node (ref "U11") (pin "15") (pinfunction "Q0_15") (pintype "output"))
    )
    (net (code "89") (name "Net-(U11-Q1)") (class "Default")
      (node (ref "RN5") (pin "7") (pinfunction "7_7") (pintype "passive"))
      (node (ref "U11") (pin "1") (pinfunction "Q1_1") (pintype "output"))
    )
    (net (code "90") (name "Net-(U11-Q2)") (class "Default")
      (node (ref "RN5") (pin "6") (pinfunction "6_6") (pintype "passive"))
      (node (ref "U11") (pin "2") (pinfunction "Q2_2") (pintype "output"))
    )
    (net (code "91") (name "Net-(U11-Q3)") (class "Default")
      (node (ref "RN5") (pin "5") (pinfunction "5_5") (pintype "passive"))
      (node (ref "U11") (pin "3") (pinfunction "Q3_3") (pintype "output"))
    )
    (net (code "92") (name "Net-(U11-Q4)") (class "Default")
      (node (ref "RN5") (pin "4") (pinfunction "4_4") (pintype "passive"))
      (node (ref "U11") (pin "4") (pinfunction "Q4_4") (pintype "output"))
    )
    (net (code "93") (name "Net-(U11-Q5)") (class "Default")
      (node (ref "RN5") (pin "3") (pinfunction "3_3") (pintype "passive"))
      (node (ref "U11") (pin "5") (pinfunction "Q5_5") (pintype "output"))
    )
    (net (code "94") (name "Net-(U11-Q6)") (class "Default")
      (node (ref "RN5") (pin "2") (pinfunction "2_2") (pintype "passive"))
      (node (ref "U11") (pin "6") (pinfunction "Q6_6") (pintype "output"))
    )
    (net (code "95") (name "Net-(U11-Q7)") (class "Default")
      (node (ref "RN5") (pin "1") (pinfunction "1_1") (pintype "passive"))
      (node (ref "U11") (pin "7") (pinfunction "Q7_7") (pintype "output"))
    )
    (net (code "96") (name "Net-(U11-Q7S)") (class "Default")
      (node (ref "U11") (pin "9") (pinfunction "Q7S_9") (pintype "output"))
      (node (ref "U13") (pin "14") (pinfunction "DS_14") (pintype "input"))
    )
    (net (code "97") (name "Net-(U13-Q0)") (class "Default")
      (node (ref "RN6") (pin "8") (pinfunction "8_8") (pintype "passive"))
      (node (ref "U13") (pin "15") (pinfunction "Q0_15") (pintype "output"))
    )
    (net (code "98") (name "Net-(U13-Q1)") (class "Default")
      (node (ref "RN6") (pin "7") (pinfunction "7_7") (pintype "passive"))
      (node (ref "U13") (pin "1") (pinfunction "Q1_1") (pintype "output"))
    )
    (net (code "99") (name "Net-(U13-Q2)") (class "Default")
      (node (ref "RN6") (pin "6") (pinfunction "6_6") (pintype "passive"))
      (node (ref "U13") (pin "2") (pinfunction "Q2_2") (pintype "output"))
    )
    (net (code "100") (name "Net-(U13-Q3)") (class "Default")
      (node (ref "RN6") (pin "5") (pinfunction "5_5") (pintype "passive"))
      (node (ref "U13") (pin "3") (pinfunction "Q3_3") (pintype "output"))
    )
    (net (code "101") (name "Net-(U13-Q4)") (class "Default")
      (node (ref "RN6") (pin "4") (pinfunction "4_4") (pintype "passive"))
      (node (ref "U13") (pin "4") (pinfunction "Q4_4") (pintype "output"))
    )
    (net (code "102") (name "Net-(U13-Q5)") (class "Default")
      (node (ref "RN6") (pin "3") (pinfunction "3_3") (pintype "passive"))
      (node (ref "U13") (pin "5") (pinfunction "Q5_5") (pintype "output"))
    )
    (net (code "103") (name "Net-(U13-Q6)") (class "Default")
      (node (ref "RN6") (pin "2") (pinfunction "2_2") (pintype "passive"))
      (node (ref "U13") (pin "6") (pinfunction "Q6_6") (pintype "output"))
    )
    (net (code "104") (name "Net-(U13-Q7)") (class "Default")
      (node (ref "RN6") (pin "1") (pinfunction "1_1") (pintype "passive"))
      (node (ref "U13") (pin "7") (pinfunction "Q7_7") (pintype "output"))
    )
    (net (code "105") (name "Net-(U13-Q7S)") (class "Default")
      (node (ref "U13") (pin "9") (pinfunction "Q7S_9") (pintype "output"))
      (node (ref "U14") (pin "14") (pinfunction "DS_14") (pintype "input"))
    )
    (net (code "106") (name "Net-(U14-Q0)") (class "Default")
      (node (ref "RN7") (pin "8") (pinfunction "8_8") (pintype "passive"))
      (node (ref "U14") (pin "15") (pinfunction "Q0_15") (pintype "output"))
    )
    (net (code "107") (name "Net-(U14-Q1)") (class "Default")
      (node (ref "RN7") (pin "7") (pinfunction "7_7") (pintype "passive"))
      (node (ref "U14") (pin "1") (pinfunction "Q1_1") (pintype "output"))
    )
    (net (code "108") (name "Net-(U14-Q2)") (class "Default")
      (node (ref "RN7") (pin "6") (pinfunction "6_6") (pintype "passive"))
      (node (ref "U14") (pin "2") (pinfunction "Q2_2") (pintype "output"))
    )
    (net (code "109") (name "Net-(U14-Q3)") (class "Default")
      (node (ref "RN7") (pin "5") (pinfunction "5_5") (pintype "passive"))
      (node (ref "U14") (pin "3") (pinfunction "Q3_3") (pintype "output"))
    )
    (net (code "110") (name "Net-(U14-Q4)") (class "Default")
      (node (ref "RN7") (pin "4") (pinfunction "4_4") (pintype "passive"))
      (node (ref "U14") (pin "4") (pinfunction "Q4_4") (pintype "output"))
    )
    (net (code "111") (name "Net-(U14-Q5)") (class "Default")
      (node (ref "RN7") (pin "3") (pinfunction "3_3") (pintype "passive"))
      (node (ref "U14") (pin "5") (pinfunction "Q5_5") (pintype "output"))
    )
    (net (code "112") (name "Net-(U14-Q6)") (class "Default")
      (node (ref "RN7") (pin "2") (pinfunction "2_2") (pintype "passive"))
      (node (ref "U14") (pin "6") (pinfunction "Q6_6") (pintype "output"))
    )
    (net (code "113") (name "Net-(U14-Q7)") (class "Default")
      (node (ref "RN7") (pin "1") (pinfunction "1_1") (pintype "passive"))
      (node (ref "U14") (pin "7") (pinfunction "Q7_7") (pintype "output"))
    )
    (net (code "114") (name "Net-(U14-Q7S)") (class "Default")
      (node (ref "U14") (pin "9") (pinfunction "Q7S_9") (pintype "output"))
      (node (ref "U15") (pin "14") (pinfunction "DS_14") (pintype "input"))
    )
    (net (code "115") (name "Net-(U15-Q0)") (class "Default")
      (node (ref "RN8") (pin "8") (pinfunction "8_8") (pintype "passive"))
      (node (ref "U15") (pin "15") (pinfunction "Q0_15") (pintype "output"))
    )
    (net (code "116") (name "Net-(U15-Q1)") (class "Default")
      (node (ref "RN8") (pin "7") (pinfunction "7_7") (pintype "passive"))
      (node (ref "U15") (pin "1") (pinfunction "Q1_1") (pintype "output"))
    )
    (net (code "117") (name "Net-(U15-Q2)") (class "Default")
      (node (ref "RN8") (pin "6") (pinfunction "6_6") (pintype "passive"))
      (node (ref "U15") (pin "2") (pinfunction "Q2_2") (pintype "output"))
    )
    (net (code "118") (name "Net-(U15-Q3)") (class "Default")
      (node (ref "RN8") (pin "5") (pinfunction "5_5") (pintype "passive"))
      (node (ref "U15") (pin "3") (pinfunction "Q3_3") (pintype "output"))
    )
    (net (code "119") (name "Net-(U15-Q4)") (class "Default")
      (node (ref "RN8") (pin "4") (pinfunction "4_4") (pintype "passive"))
      (node (ref "U15") (pin "4") (pinfunction "Q4_4") (pintype "output"))
    )
    (net (code "120") (name "Net-(U15-Q5)") (class "Default")
      (node (ref "RN8") (pin "3") (pinfunction "3_3") (pintype "passive"))
      (node (ref "U15") (pin "5") (pinfunction "Q5_5") (pintype "output"))
    )
    (net (code "121") (name "Net-(U15-Q6)") (class "Default")
      (node (ref "RN8") (pin "2") (pinfunction "2_2") (pintype "passive"))
      (node (ref "U15") (pin "6") (pinfunction "Q6_6") (pintype "output"))
    )
    (net (code "122") (name "Net-(U15-Q7)") (class "Default")
      (node (ref "RN8") (pin "1") (pinfunction "1_1") (pintype "passive"))
      (node (ref "U15") (pin "7") (pinfunction "Q7_7") (pintype "output"))
    )
    (net (code "123") (name "Net-(U15-Q7S)") (class "Default")
      (node (ref "U15") (pin "9") (pinfunction "Q7S_9") (pintype "output"))
      (node (ref "U16") (pin "14") (pinfunction "DS_14") (pintype "input"))
    )
    (net (code "124") (name "Net-(U16-Q0)") (class "Default")
      (node (ref "RN9") (pin "8") (pinfunction "8_8") (pintype "passive"))
      (node (ref "U16") (pin "15") (pinfunction "Q0_15") (pintype "output"))
    )
    (net (code "125") (name "Net-(U16-Q1)") (class "Default")
      (node (ref "RN9") (pin "7") (pinfunction "7_7") (pintype "passive"))
      (node (ref "U16") (pin "1") (pinfunction "Q1_1") (pintype "output"))
    )
    (net (code "126") (name "Net-(U16-Q2)") (class "Default")
      (node (ref "RN9") (pin "6") (pinfunction "6_6") (pintype "passive"))
      (node (ref "U16") (pin "2") (pinfunction "Q2_2") (pintype "output"))
    )
    (net (code "127") (name "Net-(U16-Q3)") (class "Default")
      (node (ref "RN9") (pin "5") (pinfunction "5_5") (pintype "passive"))
      (node (ref "U16") (pin "3") (pinfunction "Q3_3") (pintype "output"))
    )
    (net (code "128") (name "Net-(U16-Q4)") (class "Default")
      (node (ref "RN9") (pin "4") (pinfunction "4_4") (pintype "passive"))
      (node (ref "U16") (pin "4") (pinfunction "Q4_4") (pintype "output"))
    )
    (net (code "129") (name "Net-(U16-Q5)") (class "Default")
      (node (ref "RN9") (pin "3") (pinfunction "3_3") (pintype "passive"))
      (node (ref "U16") (pin "5") (pinfunction "Q5_5") (pintype "output"))
    )
    (net (code "130") (name "Net-(U16-Q6)") (class "Default")
      (node (ref "RN9") (pin "2") (pinfunction "2_2") (pintype "passive"))
      (node (ref "U16") (pin "6") (pinfunction "Q6_6") (pintype "output"))
    )
    (net (code "131") (name "Net-(U16-Q7)") (class "Default")
      (node (ref "RN9") (pin "1") (pinfunction "1_1") (pintype "passive"))
      (node (ref "U16") (pin "7") (pinfunction "Q7_7") (pintype "output"))
    )
    (net (code "132") (name "Net-(U16-Q7S)") (class "Default")
      (node (ref "U16") (pin "9") (pinfunction "Q7S_9") (pintype "output"))
      (node (ref "U17") (pin "14") (pinfunction "DS_14") (pintype "input"))
    )
    (net (code "133") (name "Net-(U17-Q0)") (class "Default")
      (node (ref "RN10") (pin "8") (pinfunction "8_8") (pintype "passive"))
      (node (ref "U17") (pin "15") (pinfunction "Q0_15") (pintype "output"))
    )
    (net (code "134") (name "Net-(U17-Q1)") (class "Default")
      (node (ref "RN10") (pin "7") (pinfunction "7_7") (pintype "passive"))
      (node (ref "U17") (pin "1") (pinfunction "Q1_1") (pintype "output"))
    )
    (net (code "135") (name "Net-(U17-Q2)") (class "Default")
      (node (ref "RN10") (pin "6") (pinfunction "6_6") (pintype "passive"))
      (node (ref "U17") (pin "2") (pinfunction "Q2_2") (pintype "output"))
    )
    (net (code "136") (name "Net-(U17-Q3)") (class "Default")
      (node (ref "RN10") (pin "5") (pinfunction "5_5") (pintype "passive"))
      (node (ref "U17") (pin "3") (pinfunction "Q3_3") (pintype "output"))
    )
    (net (code "137") (name "Net-(U17-Q4)") (class "Default")
      (node (ref "RN10") (pin "4") (pinfunction "4_4") (pintype "passive"))
      (node (ref "U17") (pin "4") (pinfunction "Q4_4") (pintype "output"))
    )
    (net (code "138") (name "Net-(U17-Q5)") (class "Default")
      (node (ref "RN10") (pin "3") (pinfunction "3_3") (pintype "passive"))
      (node (ref "U17") (pin "5") (pinfunction "Q5_5") (pintype "output"))
    )
    (net (code "139") (name "Net-(U17-Q6)") (class "Default")
      (node (ref "RN10") (pin "2") (pinfunction "2_2") (pintype "passive"))
      (node (ref "U17") (pin "6") (pinfunction "Q6_6") (pintype "output"))
    )
    (net (code "140") (name "Net-(U17-Q7)") (class "Default")
      (node (ref "RN10") (pin "1") (pinfunction "1_1") (pintype "passive"))
      (node (ref "U17") (pin "7") (pinfunction "Q7_7") (pintype "output"))
    )
    (net (code "141") (name "Net-(U17-Q7S)") (class "Default")
      (node (ref "U17") (pin "9") (pinfunction "Q7S_9") (pintype "output"))
      (node (ref "U18") (pin "14") (pinfunction "DS_14") (pintype "input"))
    )
    (net (code "142") (name "Net-(U18-Q0)") (class "Default")
      (node (ref "RN11") (pin "8") (pinfunction "8_8") (pintype "passive"))
      (node (ref "U18") (pin "15") (pinfunction "Q0_15") (pintype "output"))
    )
    (net (code "143") (name "Net-(U18-Q1)") (class "Default")
      (node (ref "RN11") (pin "7") (pinfunction "7_7") (pintype "passive"))
      (node (ref "U18") (pin "1") (pinfunction "Q1_1") (pintype "output"))
    )
    (net (code "144") (name "Net-(U18-Q2)") (class "Default")
      (node (ref "RN11") (pin "6") (pinfunction "6_6") (pintype "passive"))
      (node (ref "U18") (pin "2") (pinfunction "Q2_2") (pintype "output"))
    )
    (net (code "145") (name "Net-(U18-Q3)") (class "Default")
      (node (ref "RN11") (pin "5") (pinfunction "5_5") (pintype "passive"))
      (node (ref "U18") (pin "3") (pinfunction "Q3_3") (pintype "output"))
    )
    (net (code "146") (name "Net-(U18-Q4)") (class "Default")
      (node (ref "RN11") (pin "4") (pinfunction "4_4") (pintype "passive"))
      (node (ref "U18") (pin "4") (pinfunction "Q4_4") (pintype "output"))
    )
    (net (code "147") (name "Net-(U18-Q5)") (class "Default")
      (node (ref "RN11") (pin "3") (pinfunction "3_3") (pintype "passive"))
      (node (ref "U18") (pin "5") (pinfunction "Q5_5") (pintype "output"))
    )
    (net (code "148") (name "Net-(U18-Q6)") (class "Default")
      (node (ref "RN11") (pin "2") (pinfunction "2_2") (pintype "passive"))
      (node (ref "U18") (pin "6") (pinfunction "Q6_6") (pintype "output"))
    )
    (net (code "149") (name "Net-(U18-Q7)") (class "Default")
      (node (ref "RN11") (pin "1") (pinfunction "1_1") (pintype "passive"))
      (node (ref "U18") (pin "7") (pinfunction "Q7_7") (pintype "output"))
    )
    (net (code "150") (name "Net-(U18-Q7S)") (class "Default")
      (node (ref "U18") (pin "9") (pinfunction "Q7S_9") (pintype "output"))
      (node (ref "U19") (pin "14") (pinfunction "DS_14") (pintype "input"))
    )
    (net (code "151") (name "Net-(U19-Q0)") (class "Default")
      (node (ref "RN12") (pin "8") (pinfunction "8_8") (pintype "passive"))
      (node (ref "U19") (pin "15") (pinfunction "Q0_15") (pintype "output"))
    )
    (net (code "152") (name "Net-(U19-Q1)") (class "Default")
      (node (ref "RN12") (pin "7") (pinfunction "7_7") (pintype "passive"))
      (node (ref "U19") (pin "1") (pinfunction "Q1_1") (pintype "output"))
    )
    (net (code "153") (name "Net-(U19-Q2)") (class "Default")
      (node (ref "RN12") (pin "6") (pinfunction "6_6") (pintype "passive"))
      (node (ref "U19") (pin "2") (pinfunction "Q2_2") (pintype "output"))
    )
    (net (code "154") (name "Net-(U19-Q3)") (class "Default")
      (node (ref "RN12") (pin "5") (pinfunction "5_5") (pintype "passive"))
      (node (ref "U19") (pin "3") (pinfunction "Q3_3") (pintype "output"))
    )
    (net (code "155") (name "Net-(U19-Q4)") (class "Default")
      (node (ref "RN12") (pin "4") (pinfunction "4_4") (pintype "passive"))
      (node (ref "U19") (pin "4") (pinfunction "Q4_4") (pintype "output"))
    )
    (net (code "156") (name "Net-(U19-Q5)") (class "Default")
      (node (ref "RN12") (pin "3") (pinfunction "3_3") (pintype "passive"))
      (node (ref "U19") (pin "5") (pinfunction "Q5_5") (pintype "output"))
    )
    (net (code "157") (name "Net-(U19-Q6)") (class "Default")
      (node (ref "RN12") (pin "2") (pinfunction "2_2") (pintype "passive"))
      (node (ref "U19") (pin "6") (pinfunction "Q6_6") (pintype "output"))
    )
    (net (code "158") (name "Net-(U19-Q7)") (class "Default")
      (node (ref "RN12") (pin "1") (pinfunction "1_1") (pintype "passive"))
      (node (ref "U19") (pin "7") (pinfunction "Q7_7") (pintype "output"))
    )
    (net (code "159") (name "Net-(U19-Q7S)") (class "Default")
      (node (ref "U19") (pin "9") (pinfunction "Q7S_9") (pintype "output"))
      (node (ref "U20") (pin "14") (pinfunction "DS_14") (pintype "input"))
    )
    (net (code "160") (name "Net-(U20-Q0)") (class "Default")
      (node (ref "RN13") (pin "8") (pinfunction "8_8") (pintype "passive"))
      (node (ref "U20") (pin "15") (pinfunction "Q0_15") (pintype "output"))
    )
    (net (code "161") (name "Net-(U20-Q1)") (class "Default")
      (node (ref "RN13") (pin "7") (pinfunction "7_7") (pintype "passive"))
      (node (ref "U20") (pin "1") (pinfunction "Q1_1") (pintype "output"))
    )
    (net (code "162") (name "Net-(U20-Q2)") (class "Default")
      (node (ref "RN13") (pin "6") (pinfunction "6_6") (pintype "passive"))
      (node (ref "U20") (pin "2") (pinfunction "Q2_2") (pintype "output"))
    )
    (net (code "163") (name "Net-(U20-Q3)") (class "Default")
      (node (ref "RN13") (pin "5") (pinfunction "5_5") (pintype "passive"))
      (node (ref "U20") (pin "3") (pinfunction "Q3_3") (pintype "output"))
    )
    (net (code "164") (name "Net-(U20-Q4)") (class "Default")
      (node (ref "RN13") (pin "4") (pinfunction "4_4") (pintype "passive"))
      (node (ref "U20") (pin "4") (pinfunction "Q4_4") (pintype "output"))
    )
    (net (code "165") (name "Net-(U20-Q5)") (class "Default")
      (node (ref "RN13") (pin "3") (pinfunction "3_3") (pintype "passive"))
      (node (ref "U20") (pin "5") (pinfunction "Q5_5") (pintype "output"))
    )
    (net (code "166") (name "Net-(U20-Q6)") (class "Default")
      (node (ref "RN13") (pin "2") (pinfunction "2_2") (pintype "passive"))
      (node (ref "U20") (pin "6") (pinfunction "Q6_6") (pintype "output"))
    )
    (net (code "167") (name "Net-(U20-Q7)") (class "Default")
      (node (ref "RN13") (pin "1") (pinfunction "1_1") (pintype "passive"))
      (node (ref "U20") (pin "7") (pinfunction "Q7_7") (pintype "output"))
    )
    (net (code "168") (name "Net-(U20-Q7S)") (class "Default")
      (node (ref "U20") (pin "9") (pinfunction "Q7S_9") (pintype "output"))
      (node (ref "U21") (pin "14") (pinfunction "DS_14") (pintype "input"))
    )
    (net (code "169") (name "Net-(U21-Q0)") (class "Default")
      (node (ref "RN14") (pin "8") (pinfunction "8_8") (pintype "passive"))
      (node (ref "U21") (pin "15") (pinfunction "Q0_15") (pintype "output"))
    )
    (net (code "170") (name "Net-(U21-Q1)") (class "Default")
      (node (ref "RN14") (pin "7") (pinfunction "7_7") (pintype "passive"))
      (node (ref "U21") (pin "1") (pinfunction "Q1_1") (pintype "output"))
    )
    (net (code "171") (name "Net-(U21-Q2)") (class "Default")
      (node (ref "RN14") (pin "6") (pinfunction "6_6") (pintype "passive"))
      (node (ref "U21") (pin "2") (pinfunction "Q2_2") (pintype "output"))
    )
    (net (code "172") (name "Net-(U21-Q3)") (class "Default")
      (node (ref "RN14") (pin "5") (pinfunction "5_5") (pintype "passive"))
      (node (ref "U21") (pin "3") (pinfunction "Q3_3") (pintype "output"))
    )
    (net (code "173") (name "Net-(U21-Q4)") (class "Default")
      (node (ref "RN14") (pin "4") (pinfunction "4_4") (pintype "passive"))
      (node (ref "U21") (pin "4") (pinfunction "Q4_4") (pintype "output"))
    )
    (net (code "174") (name "Net-(U21-Q5)") (class "Default")
      (node (ref "RN14") (pin "3") (pinfunction "3_3") (pintype "passive"))
      (node (ref "U21") (pin "5") (pinfunction "Q5_5") (pintype "output"))
    )
    (net (code "175") (name "Net-(U21-Q6)") (class "Default")
      (node (ref "RN14") (pin "2") (pinfunction "2_2") (pintype "passive"))
      (node (ref "U21") (pin "6") (pinfunction "Q6_6") (pintype "output"))
    )
    (net (code "176") (name "Net-(U21-Q7)") (class "Default")
      (node (ref "RN14") (pin "1") (pinfunction "1_1") (pintype "passive"))
      (node (ref "U21") (pin "7") (pinfunction "Q7_7") (pintype "output"))
    )
    (net (code "177") (name "unconnected-(U21-GND-Pad8)") (class "Default")
      (node (ref "U21") (pin "8") (pinfunction "GND_8") (pintype "power_in"))
    )
    (net (code "178") (name "unconnected-(U21-Q7S-Pad9)") (class "Default")
      (node (ref "U21") (pin "9") (pinfunction "Q7S_9") (pintype "output"))
    )
  )
)
